# POT_2x8.net
KiCad netlist of a schematic drawn in Altium Designer
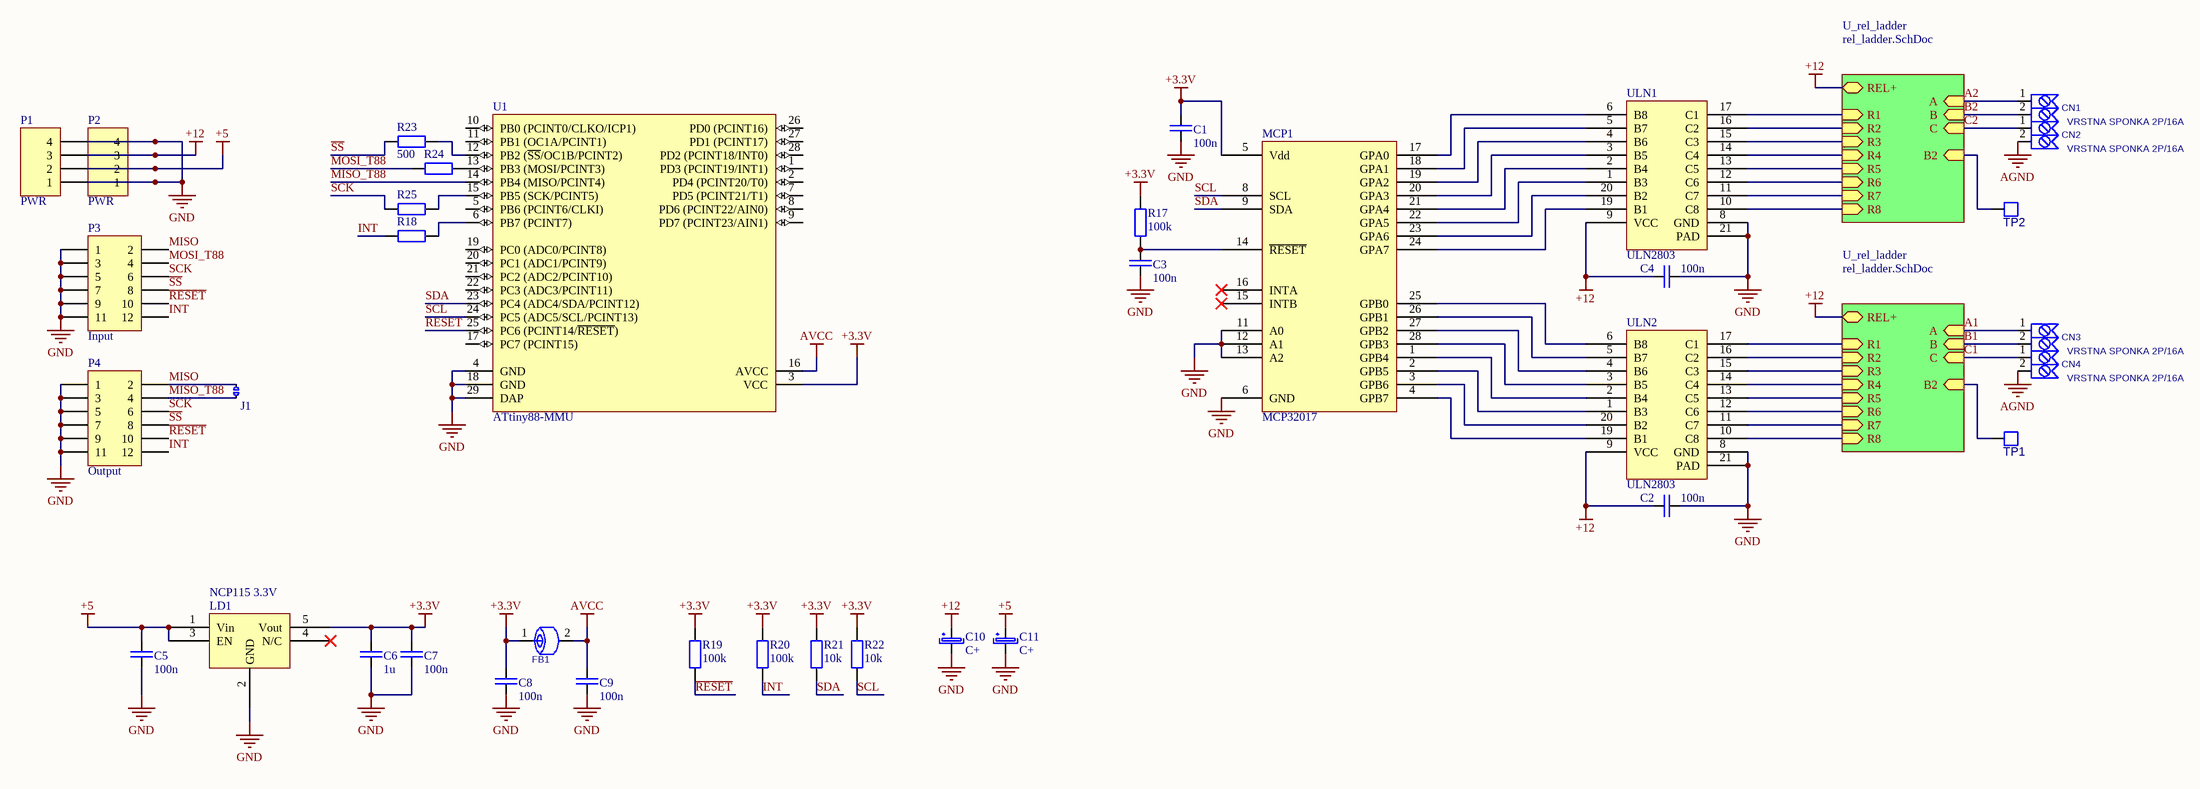
[diagram p0: POT 2x8.SchDoc]

(export (version "E")
  (design (tool "Eeschema 10.0.6"))
  (components
    (comp (ref "C1")
      (value "100n")
      (footprint "R1005_0402i_L")
      (description "Capacitor")
      (libsource (lib "General") (part "C"))
    )
    (comp (ref "C2")
      (value "100n")
      (footprint "R1005_0402i_L")
      (description "Capacitor")
      (libsource (lib "General") (part "C"))
    )
    (comp (ref "C3")
      (value "100n")
      (footprint "R1005_0402i_L")
      (description "Capacitor")
      (libsource (lib "General") (part "C"))
    )
    (comp (ref "C4")
      (value "100n")
      (footprint "R1005_0402i_L")
      (description "Capacitor")
      (libsource (lib "General") (part "C"))
    )
    (comp (ref "C5")
      (value "100n")
      (footprint "R1005_0402i_L")
      (description "Capacitor")
      (libsource (lib "General") (part "C"))
    )
    (comp (ref "C6")
      (value "1u")
      (footprint "C1608_0603I_L")
      (description "Capacitor")
      (libsource (lib "General") (part "C"))
    )
    (comp (ref "C7")
      (value "100n")
      (footprint "R1005_0402i_L")
      (description "Capacitor")
      (libsource (lib "General") (part "C"))
    )
    (comp (ref "C8")
      (value "100n")
      (footprint "R1005_0402i_L")
      (description "Capacitor")
      (libsource (lib "General") (part "C"))
    )
    (comp (ref "C9")
      (value "100n")
      (footprint "R1005_0402i_L")
      (description "Capacitor")
      (libsource (lib "General") (part "C"))
    )
    (comp (ref "C10")
      (value "C+")
      (footprint "C AlElko 5x11 R2")
      (description "Capacitor Polarized")
      (libsource (lib "General") (part "C+"))
    )
    (comp (ref "C11")
      (value "C+")
      (footprint "C AlElko 5x11 R2")
      (description "Capacitor Polarized")
      (libsource (lib "General") (part "C+"))
    )
    (comp (ref "CN1")
      (value "VRSTNA SPONKA 2P/16A")
      (footprint "VRSTNA SPONKA 2P/16A")
      (libsource (lib "Kon_Tipk") (part "VRSTNA SPONKA 2P/16A"))
    )
    (comp (ref "CN2")
      (value "VRSTNA SPONKA 2P/16A")
      (footprint "VRSTNA SPONKA 2P/16A")
      (libsource (lib "Kon_Tipk") (part "VRSTNA SPONKA 2P/16A"))
    )
    (comp (ref "CN3")
      (value "VRSTNA SPONKA 2P/16A")
      (footprint "VRSTNA SPONKA 2P/16A")
      (libsource (lib "Kon_Tipk") (part "VRSTNA SPONKA 2P/16A"))
    )
    (comp (ref "CN4")
      (value "VRSTNA SPONKA 2P/16A")
      (footprint "VRSTNA SPONKA 2P/16A")
      (libsource (lib "Kon_Tipk") (part "VRSTNA SPONKA 2P/16A"))
    )
    (comp (ref "FB1")
      (value "FERITTE BEAD")
      (footprint "R1608_0603I_L")
      (libsource (lib "General") (part "FERITTE BEAD"))
    )
    (comp (ref "J1")
      (value "Terminator")
      (footprint "solderJumper")
      (libsource (lib "Kon_Tipk") (part "JMP_mini"))
    )
    (comp (ref "LD1")
      (value "NCP115 3.3V")
      (footprint "TSOP95P280X110-6L")
      (libsource (lib "led_ring") (part "NCP115 3.3V"))
    )
    (comp (ref "MCP1")
      (value "MCP32017")
      (footprint "MCP23017 QFN")
      (libsource (lib "Schlib1") (part "MCP32017"))
    )
    (comp (ref "P1")
      (value "PWR")
      (footprint "HDR1X4")
      (description "Header, 4-Pin")
      (fields (field (name "PUBLISHER") "Altium Limited"))
      (libsource (lib "Miscellaneous Connectors") (part "Header 4"))
    )
    (comp (ref "P2")
      (value "PWR")
      (footprint "HDR1X4")
      (description "Header, 4-Pin")
      (fields (field (name "PUBLISHER") "Altium Limited"))
      (libsource (lib "Miscellaneous Connectors") (part "Header 4"))
    )
    (comp (ref "P3")
      (value "Input")
      (footprint "1.27mm SMD conn")
      (description "Header, 6-Pin, Dual row")
      (fields (field (name "PUBLISHER") "Altium Limited"))
      (libsource (lib "Miscellaneous Connectors") (part "Header 6X2"))
    )
    (comp (ref "P4")
      (value "Output")
      (footprint "1.27mm SMD conn")
      (description "Header, 6-Pin, Dual row")
      (fields (field (name "PUBLISHER") "Altium Limited"))
      (libsource (lib "Miscellaneous Connectors") (part "Header 6X2"))
    )
    (comp (ref "R17")
      (value "100k")
      (footprint "R1005_0402i_L")
      (description "R")
      (libsource (lib "General") (part "R"))
    )
    (comp (ref "R18")
      (value "500")
      (footprint "R1005_0402i_L")
      (description "R")
      (libsource (lib "General") (part "R"))
    )
    (comp (ref "R19")
      (value "100k")
      (footprint "R1005_0402i_L")
      (description "R")
      (libsource (lib "General") (part "R"))
    )
    (comp (ref "R20")
      (value "100k")
      (footprint "R1005_0402i_L")
      (description "R")
      (libsource (lib "General") (part "R"))
    )
    (comp (ref "R21")
      (value "10k")
      (footprint "R1005_0402i_L")
      (description "R")
      (libsource (lib "General") (part "R"))
    )
    (comp (ref "R22")
      (value "10k")
      (footprint "R1005_0402i_L")
      (description "R")
      (libsource (lib "General") (part "R"))
    )
    (comp (ref "R23")
      (value "500")
      (footprint "R1005_0402i_L")
      (description "R")
      (libsource (lib "General") (part "R"))
    )
    (comp (ref "R24")
      (value "500")
      (footprint "R1005_0402i_L")
      (description "R")
      (libsource (lib "General") (part "R"))
    )
    (comp (ref "R25")
      (value "500")
      (footprint "R1005_0402i_L")
      (description "R")
      (libsource (lib "General") (part "R"))
    )
    (comp (ref "TP1") (value "PAD") (footprint "PAD_CIRC_HOLE") (libsource (lib "General") (part "PAD")))
    (comp (ref "TP2") (value "PAD") (footprint "PAD_CIRC_HOLE") (libsource (lib "General") (part "PAD")))
    (comp (ref "U1")
      (value "ATtiny88-MMU")
      (footprint "28M1_N")
      (fields (field (name "PUBLISHER") "Altium Limited"))
      (libsource (lib "Encoder_w_LED_ring") (part "ATtiny88-MMU"))
    )
    (comp (ref "ULN1")
      (value "ULN2803")
      (footprint "QFN127P600-8N")
      (libsource (lib "Schlib1") (part "ULN2803"))
    )
    (comp (ref "ULN2")
      (value "ULN2803")
      (footprint "QFN127P600-8N")
      (libsource (lib "Schlib1") (part "ULN2803"))
    )
  )
  (nets
    (net (code "1") (name "+3.3V") (class "Default")
      (node (ref "C1") (pin "2") (pinfunction "2_2") (pintype "passive"))
      (node (ref "C6") (pin "1") (pinfunction "1_1") (pintype "passive"))
      (node (ref "C7") (pin "1") (pinfunction "1_1") (pintype "passive"))
      (node (ref "C8") (pin "1") (pinfunction "1_1") (pintype "passive"))
      (node (ref "FB1") (pin "1") (pintype "passive"))
      (node (ref "LD1") (pin "5") (pinfunction "Vout_5") (pintype "passive"))
      (node (ref "MCP1") (pin "5") (pinfunction "Vdd_5") (pintype "passive"))
      (node (ref "R17") (pin "1") (pintype "passive"))
      (node (ref "R19") (pin "1") (pintype "passive"))
      (node (ref "R20") (pin "1") (pintype "passive"))
      (node (ref "R21") (pin "1") (pintype "passive"))
      (node (ref "R22") (pin "1") (pintype "passive"))
      (node (ref "U1") (pin "3") (pinfunction "VCC_3") (pintype "power_in"))
    )
    (net (code "2") (name "+5") (class "Default")
      (node (ref "C11") (pin "1") (pinfunction "1_1") (pintype "passive"))
      (node (ref "C5") (pin "1") (pinfunction "1_1") (pintype "passive"))
      (node (ref "LD1") (pin "1") (pinfunction "Vin_1") (pintype "passive"))
      (node (ref "LD1") (pin "3") (pinfunction "EN_3") (pintype "passive"))
      (node (ref "P1") (pin "2") (pinfunction "2_2") (pintype "passive"))
      (node (ref "P2") (pin "2") (pinfunction "2_2") (pintype "passive"))
    )
    (net (code "3") (name "+12") (class "Default")
      (node (ref "C10") (pin "1") (pinfunction "1_1") (pintype "passive"))
      (node (ref "C2") (pin "1") (pinfunction "1_1") (pintype "passive"))
      (node (ref "C4") (pin "1") (pinfunction "1_1") (pintype "passive"))
      (node (ref "P1") (pin "3") (pinfunction "3_3") (pintype "passive"))
      (node (ref "P2") (pin "3") (pinfunction "3_3") (pintype "passive"))
      (node (ref "ULN1") (pin "9") (pinfunction "VCC_9") (pintype "passive"))
      (node (ref "ULN2") (pin "9") (pinfunction "VCC_9") (pintype "passive"))
    )
    (net (code "4") (name "/A1") (class "Default") (node (ref "CN3") (pin "1") (pintype "passive")))
    (net (code "5") (name "/A2") (class "Default") (node (ref "CN1") (pin "1") (pintype "passive")))
    (net (code "6") (name "/B1") (class "Default") (node (ref "CN3") (pin "2") (pintype "passive")))
    (net (code "7") (name "/B2") (class "Default") (node (ref "CN1") (pin "2") (pintype "passive")))
    (net (code "8") (name "/B2_1") (class "Default")
      (node (ref "TP1") (pin "1") (pinfunction "1_1") (pintype "passive"))
    )
    (net (code "9") (name "/B2_2") (class "Default")
      (node (ref "TP2") (pin "1") (pinfunction "1_1") (pintype "passive"))
    )
    (net (code "10") (name "/C1") (class "Default") (node (ref "CN4") (pin "1") (pintype "passive")))
    (net (code "11") (name "/C2") (class "Default") (node (ref "CN2") (pin "1") (pintype "passive")))
    (net (code "12") (name "/INT") (class "Default")
      (node (ref "P3") (pin "12") (pinfunction "12_12") (pintype "passive"))
      (node (ref "P4") (pin "12") (pinfunction "12_12") (pintype "passive"))
      (node (ref "R18") (pin "1") (pintype "passive"))
      (node (ref "R20") (pin "2") (pintype "passive"))
    )
    (net (code "13") (name "/MISO") (class "Default")
      (node (ref "J1") (pin "2") (pinfunction "2_2") (pintype "passive"))
      (node (ref "P3") (pin "2") (pinfunction "2_2") (pintype "passive"))
      (node (ref "P4") (pin "2") (pinfunction "2_2") (pintype "passive"))
    )
    (net (code "14") (name "/MISO_T88") (class "Default")
      (node (ref "J1") (pin "1") (pinfunction "1_1") (pintype "passive"))
      (node (ref "P4") (pin "4") (pinfunction "4_4") (pintype "passive"))
      (node (ref "U1") (pin "14") (pinfunction "PB4_(MISO/PCINT4)_14") (pintype "bidirectional"))
    )
    (net (code "15") (name "/MOSI_T88") (class "Default")
      (node (ref "P3") (pin "4") (pinfunction "4_4") (pintype "passive"))
      (node (ref "R24") (pin "1") (pintype "passive"))
    )
    (net (code "16") (name "/R1") (class "Default")
      (node (ref "ULN2") (pin "17") (pinfunction "C1_17") (pintype "passive"))
    )
    (net (code "17") (name "/R1_1") (class "Default")
      (node (ref "ULN1") (pin "17") (pinfunction "C1_17") (pintype "passive"))
    )
    (net (code "18") (name "/R2") (class "Default")
      (node (ref "ULN2") (pin "16") (pinfunction "C2_16") (pintype "passive"))
    )
    (net (code "19") (name "/R2_1") (class "Default")
      (node (ref "ULN1") (pin "16") (pinfunction "C2_16") (pintype "passive"))
    )
    (net (code "20") (name "/R3") (class "Default")
      (node (ref "ULN2") (pin "15") (pinfunction "C3_15") (pintype "passive"))
    )
    (net (code "21") (name "/R3_1") (class "Default")
      (node (ref "ULN1") (pin "15") (pinfunction "C3_15") (pintype "passive"))
    )
    (net (code "22") (name "/R4") (class "Default")
      (node (ref "ULN1") (pin "14") (pinfunction "C4_14") (pintype "passive"))
    )
    (net (code "23") (name "/R4_1") (class "Default")
      (node (ref "ULN2") (pin "14") (pinfunction "C4_14") (pintype "passive"))
    )
    (net (code "24") (name "/R5") (class "Default")
      (node (ref "ULN1") (pin "13") (pinfunction "C5_13") (pintype "passive"))
    )
    (net (code "25") (name "/R5_1") (class "Default")
      (node (ref "ULN2") (pin "13") (pinfunction "C5_13") (pintype "passive"))
    )
    (net (code "26") (name "/R6") (class "Default")
      (node (ref "ULN1") (pin "12") (pinfunction "C6_12") (pintype "passive"))
    )
    (net (code "27") (name "/R6_1") (class "Default")
      (node (ref "ULN2") (pin "12") (pinfunction "C6_12") (pintype "passive"))
    )
    (net (code "28") (name "/R7") (class "Default")
      (node (ref "ULN1") (pin "11") (pinfunction "C7_11") (pintype "passive"))
    )
    (net (code "29") (name "/R7_1") (class "Default")
      (node (ref "ULN2") (pin "11") (pinfunction "C7_11") (pintype "passive"))
    )
    (net (code "30") (name "/R8") (class "Default")
      (node (ref "ULN1") (pin "10") (pinfunction "C8_10") (pintype "passive"))
    )
    (net (code "31") (name "/R8_1") (class "Default")
      (node (ref "ULN2") (pin "10") (pinfunction "C8_10") (pintype "passive"))
    )
    (net (code "32") (name "/SCK") (class "Default")
      (node (ref "P3") (pin "6") (pinfunction "6_6") (pintype "passive"))
      (node (ref "P4") (pin "6") (pinfunction "6_6") (pintype "passive"))
      (node (ref "R25") (pin "1") (pintype "passive"))
    )
    (net (code "33") (name "/SCL") (class "Default")
      (node (ref "MCP1") (pin "8") (pinfunction "SCL_8") (pintype "passive"))
      (node (ref "R22") (pin "2") (pintype "passive"))
      (node (ref "U1") (pin "24") (pinfunction "PC5_(ADC5/SCL/PCINT13)_24") (pintype "bidirectional"))
    )
    (net (code "34") (name "/SDA") (class "Default")
      (node (ref "MCP1") (pin "9") (pinfunction "SDA_9") (pintype "passive"))
      (node (ref "R21") (pin "2") (pintype "passive"))
      (node (ref "U1") (pin "23") (pinfunction "PC4_(ADC4/SDA/PCINT12)_23") (pintype "bidirectional"))
    )
    (net (code "35") (name "/~{RESET}") (class "Default")
      (node (ref "P3") (pin "10") (pinfunction "10_10") (pintype "passive"))
      (node (ref "P4") (pin "10") (pinfunction "10_10") (pintype "passive"))
      (node (ref "R19") (pin "2") (pintype "passive"))
      (node (ref "U1") (pin "25") (pinfunction "PC6_(PCINT14/~{RESET})_25") (pintype "bidirectional"))
    )
    (net (code "36") (name "/~{SS}") (class "Default")
      (node (ref "P3") (pin "8") (pinfunction "8_8") (pintype "passive"))
      (node (ref "P4") (pin "8") (pinfunction "8_8") (pintype "passive"))
      (node (ref "R23") (pin "1") (pintype "passive"))
    )
    (net (code "37") (name "AGND") (class "Default")
      (node (ref "CN2") (pin "2") (pintype "passive"))
      (node (ref "CN4") (pin "2") (pintype "passive"))
    )
    (net (code "38") (name "AVCC") (class "Default")
      (node (ref "C9") (pin "1") (pinfunction "1_1") (pintype "passive"))
      (node (ref "FB1") (pin "2") (pintype "passive"))
      (node (ref "U1") (pin "16") (pinfunction "AVCC_16") (pintype "power_in"))
    )
    (net (code "39") (name "GND") (class "Default")
      (node (ref "C1") (pin "1") (pinfunction "1_1") (pintype "passive"))
      (node (ref "C10") (pin "2") (pinfunction "2_2") (pintype "passive"))
      (node (ref "C11") (pin "2") (pinfunction "2_2") (pintype "passive"))
      (node (ref "C2") (pin "2") (pinfunction "2_2") (pintype "passive"))
      (node (ref "C3") (pin "1") (pinfunction "1_1") (pintype "passive"))
      (node (ref "C4") (pin "2") (pinfunction "2_2") (pintype "passive"))
      (node (ref "C5") (pin "2") (pinfunction "2_2") (pintype "passive"))
      (node (ref "C6") (pin "2") (pinfunction "2_2") (pintype "passive"))
      (node (ref "C7") (pin "2") (pinfunction "2_2") (pintype "passive"))
      (node (ref "C8") (pin "2") (pinfunction "2_2") (pintype "passive"))
      (node (ref "C9") (pin "2") (pinfunction "2_2") (pintype "passive"))
      (node (ref "LD1") (pin "2") (pinfunction "GND_2") (pintype "passive"))
      (node (ref "MCP1") (pin "11") (pinfunction "A0_11") (pintype "passive"))
      (node (ref "MCP1") (pin "12") (pinfunction "A1_12") (pintype "passive"))
      (node (ref "MCP1") (pin "13") (pinfunction "A2_13") (pintype "passive"))
      (node (ref "MCP1") (pin "6") (pinfunction "GND_6") (pintype "passive"))
      (node (ref "P1") (pin "1") (pinfunction "1_1") (pintype "passive"))
      (node (ref "P1") (pin "4") (pinfunction "4_4") (pintype "passive"))
      (node (ref "P2") (pin "1") (pinfunction "1_1") (pintype "passive"))
      (node (ref "P2") (pin "4") (pinfunction "4_4") (pintype "passive"))
      (node (ref "P3") (pin "1") (pinfunction "1_1") (pintype "passive"))
      (node (ref "P3") (pin "11") (pinfunction "11_11") (pintype "passive"))
      (node (ref "P3") (pin "3") (pinfunction "3_3") (pintype "passive"))
      (node (ref "P3") (pin "5") (pinfunction "5_5") (pintype "passive"))
      (node (ref "P3") (pin "7") (pinfunction "7_7") (pintype "passive"))
      (node (ref "P3") (pin "9") (pinfunction "9_9") (pintype "passive"))
      (node (ref "P4") (pin "1") (pinfunction "1_1") (pintype "passive"))
      (node (ref "P4") (pin "11") (pinfunction "11_11") (pintype "passive"))
      (node (ref "P4") (pin "3") (pinfunction "3_3") (pintype "passive"))
      (node (ref "P4") (pin "5") (pinfunction "5_5") (pintype "passive"))
      (node (ref "P4") (pin "7") (pinfunction "7_7") (pintype "passive"))
      (node (ref "P4") (pin "9") (pinfunction "9_9") (pintype "passive"))
      (node (ref "U1") (pin "18") (pinfunction "GND_18") (pintype "power_in"))
      (node (ref "U1") (pin "29") (pinfunction "DAP_29") (pintype "passive"))
      (node (ref "U1") (pin "4") (pinfunction "GND_4") (pintype "power_in"))
      (node (ref "ULN1") (pin "21") (pinfunction "PAD_21") (pintype "passive"))
      (node (ref "ULN1") (pin "8") (pinfunction "GND_8") (pintype "passive"))
      (node (ref "ULN2") (pin "21") (pinfunction "PAD_21") (pintype "passive"))
      (node (ref "ULN2") (pin "8") (pinfunction "GND_8") (pintype "passive"))
    )
    (net (code "40") (name "Net-(MCP1-GPA0)") (class "Default")
      (node (ref "MCP1") (pin "17") (pinfunction "GPA0_17") (pintype "passive"))
      (node (ref "ULN1") (pin "6") (pinfunction "B8_6") (pintype "passive"))
    )
    (net (code "41") (name "Net-(MCP1-GPA1)") (class "Default")
      (node (ref "MCP1") (pin "18") (pinfunction "GPA1_18") (pintype "passive"))
      (node (ref "ULN1") (pin "5") (pinfunction "B7_5") (pintype "passive"))
    )
    (net (code "42") (name "Net-(MCP1-GPA2)") (class "Default")
      (node (ref "MCP1") (pin "19") (pinfunction "GPA2_19") (pintype "passive"))
      (node (ref "ULN1") (pin "4") (pinfunction "B6_4") (pintype "passive"))
    )
    (net (code "43") (name "Net-(MCP1-GPA3)") (class "Default")
      (node (ref "MCP1") (pin "20") (pinfunction "GPA3_20") (pintype "passive"))
      (node (ref "ULN1") (pin "3") (pinfunction "B5_3") (pintype "passive"))
    )
    (net (code "44") (name "Net-(MCP1-GPA4)") (class "Default")
      (node (ref "MCP1") (pin "21") (pinfunction "GPA4_21") (pintype "passive"))
      (node (ref "ULN1") (pin "2") (pinfunction "B4_2") (pintype "passive"))
    )
    (net (code "45") (name "Net-(MCP1-GPA5)") (class "Default")
      (node (ref "MCP1") (pin "22") (pinfunction "GPA5_22") (pintype "passive"))
      (node (ref "ULN1") (pin "1") (pinfunction "B3_1") (pintype "passive"))
    )
    (net (code "46") (name "Net-(MCP1-GPA6)") (class "Default")
      (node (ref "MCP1") (pin "23") (pinfunction "GPA6_23") (pintype "passive"))
      (node (ref "ULN1") (pin "20") (pinfunction "B2_20") (pintype "passive"))
    )
    (net (code "47") (name "Net-(MCP1-GPA7)") (class "Default")
      (node (ref "MCP1") (pin "24") (pinfunction "GPA7_24") (pintype "passive"))
      (node (ref "ULN1") (pin "19") (pinfunction "B1_19") (pintype "passive"))
    )
    (net (code "48") (name "Net-(MCP1-GPB0)") (class "Default")
      (node (ref "MCP1") (pin "25") (pinfunction "GPB0_25") (pintype "passive"))
      (node (ref "ULN2") (pin "6") (pinfunction "B8_6") (pintype "passive"))
    )
    (net (code "49") (name "Net-(MCP1-GPB1)") (class "Default")
      (node (ref "MCP1") (pin "26") (pinfunction "GPB1_26") (pintype "passive"))
      (node (ref "ULN2") (pin "5") (pinfunction "B7_5") (pintype "passive"))
    )
    (net (code "50") (name "Net-(MCP1-GPB2)") (class "Default")
      (node (ref "MCP1") (pin "27") (pinfunction "GPB2_27") (pintype "passive"))
      (node (ref "ULN2") (pin "4") (pinfunction "B6_4") (pintype "passive"))
    )
    (net (code "51") (name "Net-(MCP1-GPB3)") (class "Default")
      (node (ref "MCP1") (pin "28") (pinfunction "GPB3_28") (pintype "passive"))
      (node (ref "ULN2") (pin "3") (pinfunction "B5_3") (pintype "passive"))
    )
    (net (code "52") (name "Net-(MCP1-GPB4)") (class "Default")
      (node (ref "MCP1") (pin "1") (pinfunction "GPB4_1") (pintype "passive"))
      (node (ref "ULN2") (pin "2") (pinfunction "B4_2") (pintype "passive"))
    )
    (net (code "53") (name "Net-(MCP1-GPB5)") (class "Default")
      (node (ref "MCP1") (pin "2") (pinfunction "GPB5_2") (pintype "passive"))
      (node (ref "ULN2") (pin "1") (pinfunction "B3_1") (pintype "passive"))
    )
    (net (code "54") (name "Net-(MCP1-GPB6)") (class "Default")
      (node (ref "MCP1") (pin "3") (pinfunction "GPB6_3") (pintype "passive"))
      (node (ref "ULN2") (pin "20") (pinfunction "B2_20") (pintype "passive"))
    )
    (net (code "55") (name "Net-(MCP1-GPB7)") (class "Default")
      (node (ref "MCP1") (pin "4") (pinfunction "GPB7_4") (pintype "passive"))
      (node (ref "ULN2") (pin "19") (pinfunction "B1_19") (pintype "passive"))
    )
    (net (code "56") (name "Net-(MCP1-~{RESET})") (class "Default")
      (node (ref "C3") (pin "2") (pinfunction "2_2") (pintype "passive"))
      (node (ref "MCP1") (pin "14") (pinfunction "~{RESET}_14") (pintype "passive"))
      (node (ref "R17") (pin "2") (pintype "passive"))
    )
    (net (code "57") (name "Net-(U1-PB2_(~{SS}{slash}OC1B{slash}PCINT2))") (class "Default")
      (node (ref "R23") (pin "2") (pintype "passive"))
      (node (ref "U1") (pin "12") (pinfunction "PB2_(~{SS}/OC1B/PCINT2)_12") (pintype "bidirectional"))
    )
    (net (code "58") (name "Net-(U1-PB3_(MOSI{slash}PCINT3))") (class "Default")
      (node (ref "R24") (pin "2") (pintype "passive"))
      (node (ref "U1") (pin "13") (pinfunction "PB3_(MOSI/PCINT3)_13") (pintype "bidirectional"))
    )
    (net (code "59") (name "Net-(U1-PB5_(SCK{slash}PCINT5))") (class "Default")
      (node (ref "R25") (pin "2") (pintype "passive"))
      (node (ref "U1") (pin "15") (pinfunction "PB5_(SCK/PCINT5)_15") (pintype "bidirectional"))
    )
    (net (code "60") (name "Net-(U1-PB7_(PCINT7))") (class "Default")
      (node (ref "R18") (pin "2") (pintype "passive"))
      (node (ref "U1") (pin "6") (pinfunction "PB7_(PCINT7)_6") (pintype "bidirectional"))
    )
    (net (code "61") (name "unconnected-(LD1-N{slash}C-Pad4)") (class "Default")
      (node (ref "LD1") (pin "4") (pinfunction "N/C_4") (pintype "passive+no_connect"))
    )
    (net (code "62") (name "unconnected-(MCP1-INTA-Pad16)") (class "Default")
      (node (ref "MCP1") (pin "16") (pinfunction "INTA_16") (pintype "passive+no_connect"))
    )
    (net (code "63") (name "unconnected-(MCP1-INTB-Pad15)") (class "Default")
      (node (ref "MCP1") (pin "15") (pinfunction "INTB_15") (pintype "passive+no_connect"))
    )
    (net (code "64") (name "unconnected-(U1-PB0_(PCINT0{slash}CLKO{slash}ICP1)-Pad10)") (class "Default")
      (node (ref "U1") (pin "10") (pinfunction "PB0_(PCINT0/CLKO/ICP1)_10") (pintype "bidirectional"))
    )
    (net (code "65") (name "unconnected-(U1-PB1_(OC1A{slash}PCINT1)-Pad11)") (class "Default")
      (node (ref "U1") (pin "11") (pinfunction "PB1_(OC1A/PCINT1)_11") (pintype "bidirectional"))
    )
    (net (code "66") (name "unconnected-(U1-PB6_(PCINT6{slash}CLKI)-Pad5)") (class "Default")
      (node (ref "U1") (pin "5") (pinfunction "PB6_(PCINT6/CLKI)_5") (pintype "bidirectional"))
    )
    (net (code "67") (name "unconnected-(U1-PC0_(ADC0{slash}PCINT8)-Pad19)") (class "Default")
      (node (ref "U1") (pin "19") (pinfunction "PC0_(ADC0/PCINT8)_19") (pintype "bidirectional"))
    )
    (net (code "68") (name "unconnected-(U1-PC1_(ADC1{slash}PCINT9)-Pad20)") (class "Default")
      (node (ref "U1") (pin "20") (pinfunction "PC1_(ADC1/PCINT9)_20") (pintype "bidirectional"))
    )
    (net (code "69") (name "unconnected-(U1-PC2_(ADC2{slash}PCINT10)-Pad21)") (class "Default")
      (node (ref "U1") (pin "21") (pinfunction "PC2_(ADC2/PCINT10)_21") (pintype "bidirectional"))
    )
    (net (code "70") (name "unconnected-(U1-PC3_(ADC3{slash}PCINT11)-Pad22)") (class "Default")
      (node (ref "U1") (pin "22") (pinfunction "PC3_(ADC3/PCINT11)_22") (pintype "bidirectional"))
    )
    (net (code "71") (name "unconnected-(U1-PC7_(PCINT15)-Pad17)") (class "Default")
      (node (ref "U1") (pin "17") (pinfunction "PC7_(PCINT15)_17") (pintype "bidirectional"))
    )
    (net (code "72") (name "unconnected-(U1-PD0_(PCINT16)-Pad26)") (class "Default")
      (node (ref "U1") (pin "26") (pinfunction "PD0_(PCINT16)_26") (pintype "bidirectional"))
    )
    (net (code "73") (name "unconnected-(U1-PD1_(PCINT17)-Pad27)") (class "Default")
      (node (ref "U1") (pin "27") (pinfunction "PD1_(PCINT17)_27") (pintype "bidirectional"))
    )
    (net (code "74") (name "unconnected-(U1-PD2_(PCINT18{slash}INT0)-Pad28)") (class "Default")
      (node (ref "U1") (pin "28") (pinfunction "PD2_(PCINT18/INT0)_28") (pintype "bidirectional"))
    )
    (net (code "75") (name "unconnected-(U1-PD3_(PCINT19{slash}INT1)-Pad1)") (class "Default")
      (node (ref "U1") (pin "1") (pinfunction "PD3_(PCINT19/INT1)_1") (pintype "bidirectional"))
    )
    (net (code "76") (name "unconnected-(U1-PD4_(PCINT20{slash}T0)-Pad2)") (class "Default")
      (node (ref "U1") (pin "2") (pinfunction "PD4_(PCINT20/T0)_2") (pintype "bidirectional"))
    )
    (net (code "77") (name "unconnected-(U1-PD5_(PCINT21{slash}T1)-Pad7)") (class "Default")
      (node (ref "U1") (pin "7") (pinfunction "PD5_(PCINT21/T1)_7") (pintype "bidirectional"))
    )
    (net (code "78") (name "unconnected-(U1-PD6_(PCINT22{slash}AIN0)-Pad8)") (class "Default")
      (node (ref "U1") (pin "8") (pinfunction "PD6_(PCINT22/AIN0)_8") (pintype "bidirectional"))
    )
    (net (code "79") (name "unconnected-(U1-PD7_(PCINT23{slash}AIN1)-Pad9)") (class "Default")
      (node (ref "U1") (pin "9") (pinfunction "PD7_(PCINT23/AIN1)_9") (pintype "bidirectional"))
    )
  )
)
